# 5V-3_3V_Regulators_Pre-prototype_V2.net
KiCad netlist of a schematic drawn in EAGLE
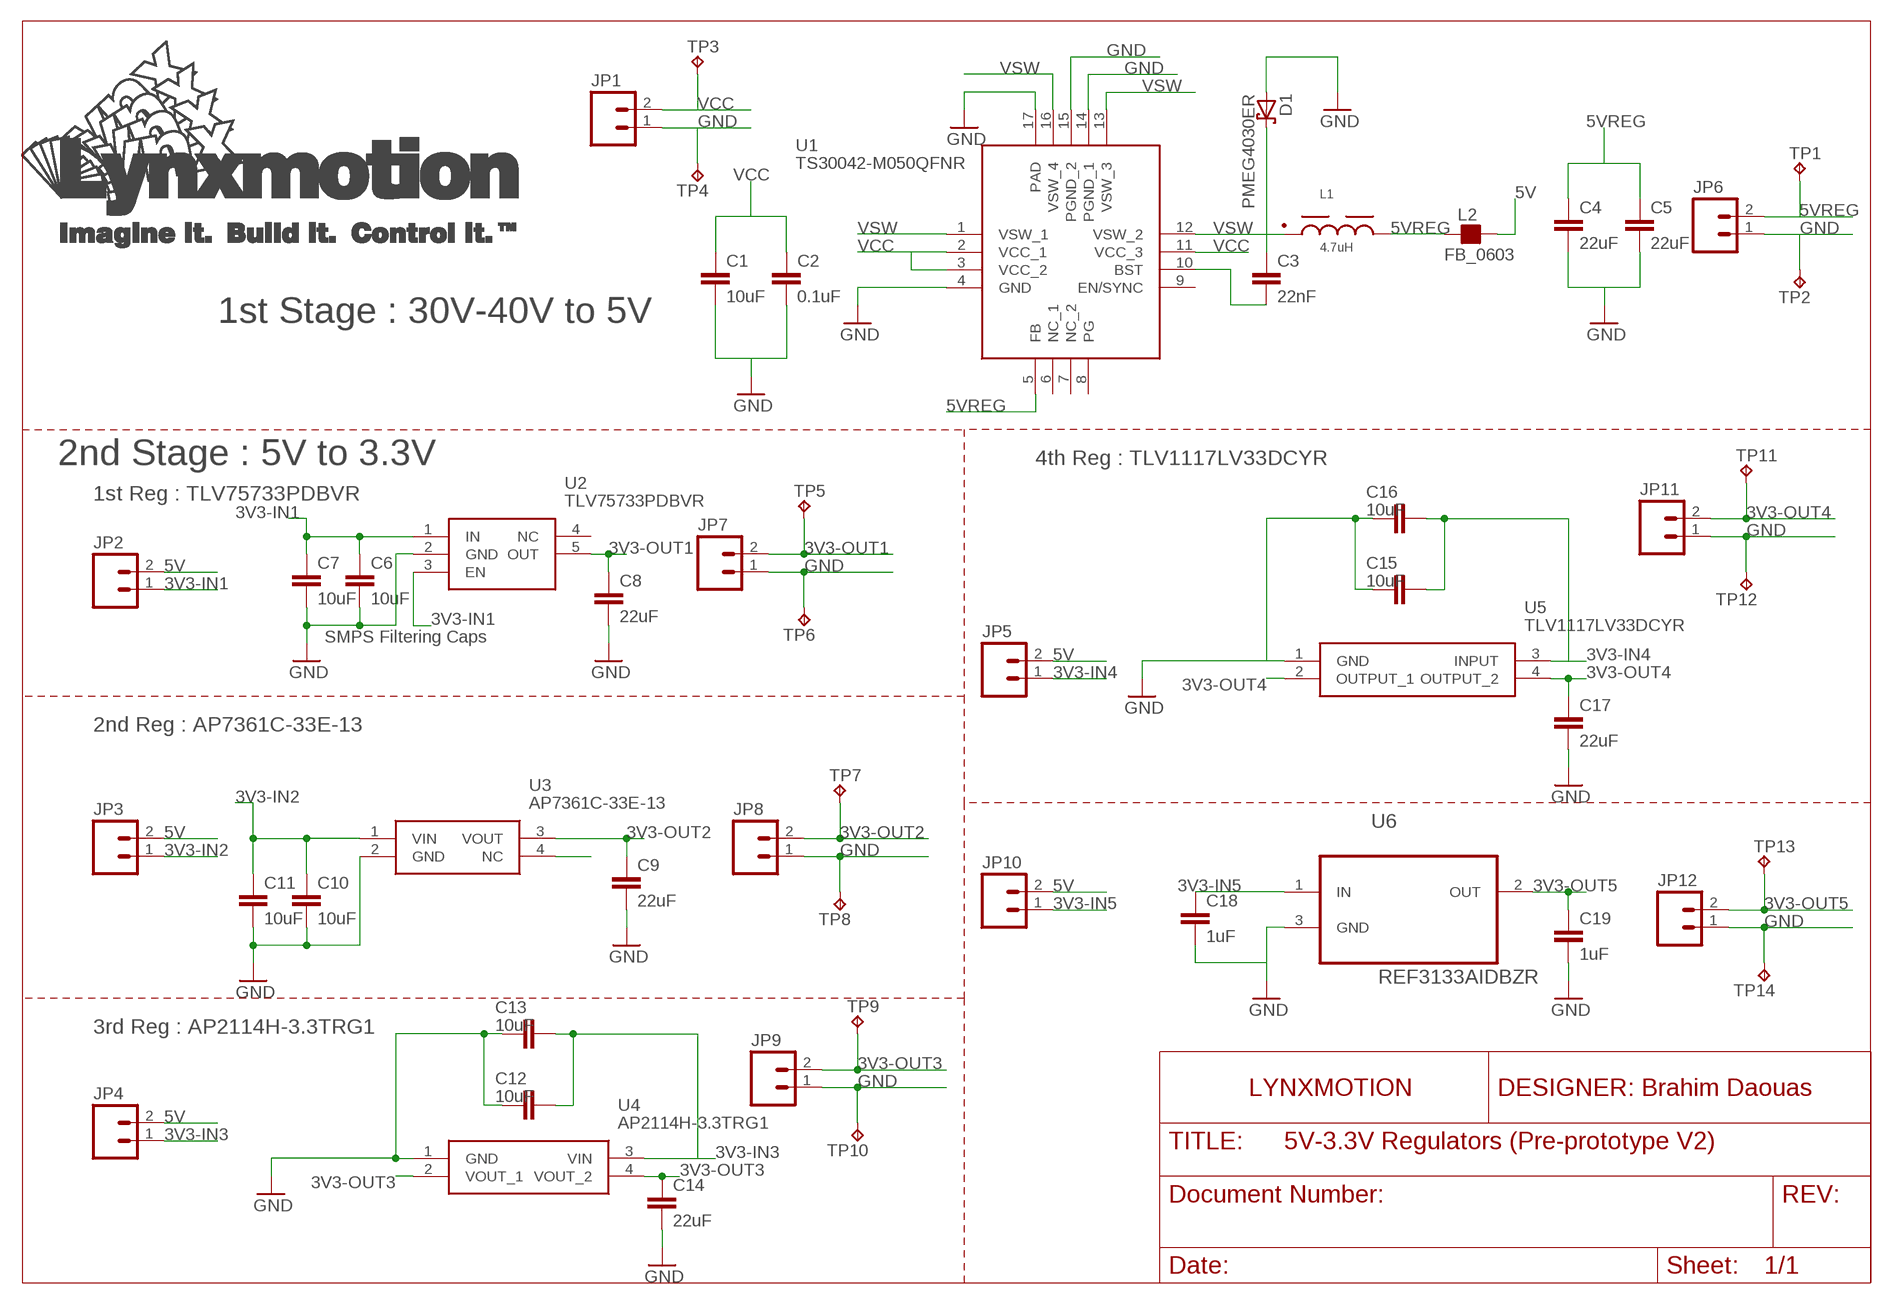
[diagram p0: schematic, sheet 1]

(export (version "E")
  (design (tool "Eeschema 10.0.6"))
  (components
    (comp (ref "C1")
      (value "10uF")
      (footprint "eagle-import:1206")
      (libsource (lib "eagle-import") (part "CAP1206"))
    )
    (comp (ref "C2")
      (value "0.1uF")
      (footprint "eagle-import:0603-CAP")
      (libsource (lib "eagle-import") (part "CAP0603-CAP"))
    )
    (comp (ref "C3")
      (value "22nF")
      (footprint "eagle-import:0402-CAP")
      (libsource (lib "eagle-import") (part "CAP0402-CAP"))
    )
    (comp (ref "C4")
      (value "22uF")
      (footprint "eagle-import:0805")
      (libsource (lib "eagle-import") (part "CAP0805"))
    )
    (comp (ref "C5")
      (value "22uF")
      (footprint "eagle-import:0805")
      (libsource (lib "eagle-import") (part "CAP0805"))
    )
    (comp (ref "C6")
      (value "10uF")
      (footprint "eagle-import:0805")
      (libsource (lib "eagle-import") (part "CAP0805"))
    )
    (comp (ref "C7")
      (value "10uF")
      (footprint "eagle-import:0805")
      (libsource (lib "eagle-import") (part "CAP0805"))
    )
    (comp (ref "C8")
      (value "22uF")
      (footprint "eagle-import:0805")
      (libsource (lib "eagle-import") (part "CAP0805"))
    )
    (comp (ref "C9")
      (value "22uF")
      (footprint "eagle-import:0805")
      (libsource (lib "eagle-import") (part "CAP0805"))
    )
    (comp (ref "C10")
      (value "10uF")
      (footprint "eagle-import:0805")
      (libsource (lib "eagle-import") (part "CAP0805"))
    )
    (comp (ref "C11")
      (value "10uF")
      (footprint "eagle-import:0805")
      (libsource (lib "eagle-import") (part "CAP0805"))
    )
    (comp (ref "C12")
      (value "10uF")
      (footprint "eagle-import:0805")
      (libsource (lib "eagle-import") (part "CAP0805"))
    )
    (comp (ref "C13")
      (value "10uF")
      (footprint "eagle-import:0805")
      (libsource (lib "eagle-import") (part "CAP0805"))
    )
    (comp (ref "C14")
      (value "22uF")
      (footprint "eagle-import:0805")
      (libsource (lib "eagle-import") (part "CAP0805"))
    )
    (comp (ref "C15")
      (value "10uF")
      (footprint "eagle-import:0805")
      (libsource (lib "eagle-import") (part "CAP0805"))
    )
    (comp (ref "C16")
      (value "10uF")
      (footprint "eagle-import:0805")
      (libsource (lib "eagle-import") (part "CAP0805"))
    )
    (comp (ref "C17")
      (value "22uF")
      (footprint "eagle-import:0805")
      (libsource (lib "eagle-import") (part "CAP0805"))
    )
    (comp (ref "C18")
      (value "1uF")
      (footprint "eagle-import:0805")
      (libsource (lib "eagle-import") (part "CAP0805"))
    )
    (comp (ref "C19")
      (value "1uF")
      (footprint "eagle-import:0805")
      (libsource (lib "eagle-import") (part "CAP0805"))
    )
    (comp (ref "D1")
      (value "PMEG4030ER")
      (footprint "eagle-import:SOD123W")
      (libsource (lib "eagle-import") (part "PMEG4030ER"))
    )
    (comp (ref "JP1")
      (value "M02PTH")
      (footprint "eagle-import:1X02")
      (libsource (lib "eagle-import") (part "M02PTH"))
    )
    (comp (ref "JP2")
      (value "M02PTH")
      (footprint "eagle-import:1X02")
      (libsource (lib "eagle-import") (part "M02PTH"))
    )
    (comp (ref "JP3")
      (value "M02PTH")
      (footprint "eagle-import:1X02")
      (libsource (lib "eagle-import") (part "M02PTH"))
    )
    (comp (ref "JP4")
      (value "M02PTH")
      (footprint "eagle-import:1X02")
      (libsource (lib "eagle-import") (part "M02PTH"))
    )
    (comp (ref "JP5")
      (value "M02PTH")
      (footprint "eagle-import:1X02")
      (libsource (lib "eagle-import") (part "M02PTH"))
    )
    (comp (ref "JP6")
      (value "M02PTH")
      (footprint "eagle-import:1X02")
      (libsource (lib "eagle-import") (part "M02PTH"))
    )
    (comp (ref "JP7")
      (value "M02PTH")
      (footprint "eagle-import:1X02")
      (libsource (lib "eagle-import") (part "M02PTH"))
    )
    (comp (ref "JP8")
      (value "M02PTH")
      (footprint "eagle-import:1X02")
      (libsource (lib "eagle-import") (part "M02PTH"))
    )
    (comp (ref "JP9")
      (value "M02PTH")
      (footprint "eagle-import:1X02")
      (libsource (lib "eagle-import") (part "M02PTH"))
    )
    (comp (ref "JP10")
      (value "M02PTH")
      (footprint "eagle-import:1X02")
      (libsource (lib "eagle-import") (part "M02PTH"))
    )
    (comp (ref "JP11")
      (value "M02PTH")
      (footprint "eagle-import:1X02")
      (libsource (lib "eagle-import") (part "M02PTH"))
    )
    (comp (ref "JP12")
      (value "M02PTH")
      (footprint "eagle-import:1X02")
      (libsource (lib "eagle-import") (part "M02PTH"))
    )
    (comp (ref "L1")
      (value "4.7uH")
      (footprint "eagle-import:WE-PD2_5848_5820")
      (libsource (lib "eagle-import") (part "WE-PD2_5848_744774047"))
    )
    (comp (ref "L2")
      (value "FB_0603")
      (footprint "eagle-import:L0603")
      (libsource (lib "eagle-import") (part "FB_0603"))
    )
    (comp (ref "TP1")
      (value "TP-040")
      (footprint "eagle-import:TP-040")
      (libsource (lib "eagle-import") (part "TP-040"))
    )
    (comp (ref "TP2")
      (value "TP-040")
      (footprint "eagle-import:TP-040")
      (libsource (lib "eagle-import") (part "TP-040"))
    )
    (comp (ref "TP3")
      (value "TP-040")
      (footprint "eagle-import:TP-040")
      (libsource (lib "eagle-import") (part "TP-040"))
    )
    (comp (ref "TP4")
      (value "TP-040")
      (footprint "eagle-import:TP-040")
      (libsource (lib "eagle-import") (part "TP-040"))
    )
    (comp (ref "TP5")
      (value "TP-040")
      (footprint "eagle-import:TP-040")
      (libsource (lib "eagle-import") (part "TP-040"))
    )
    (comp (ref "TP6")
      (value "TP-040")
      (footprint "eagle-import:TP-040")
      (libsource (lib "eagle-import") (part "TP-040"))
    )
    (comp (ref "TP7")
      (value "TP-040")
      (footprint "eagle-import:TP-040")
      (libsource (lib "eagle-import") (part "TP-040"))
    )
    (comp (ref "TP8")
      (value "TP-040")
      (footprint "eagle-import:TP-040")
      (libsource (lib "eagle-import") (part "TP-040"))
    )
    (comp (ref "TP9")
      (value "TP-040")
      (footprint "eagle-import:TP-040")
      (libsource (lib "eagle-import") (part "TP-040"))
    )
    (comp (ref "TP10")
      (value "TP-040")
      (footprint "eagle-import:TP-040")
      (libsource (lib "eagle-import") (part "TP-040"))
    )
    (comp (ref "TP11")
      (value "TP-040")
      (footprint "eagle-import:TP-040")
      (libsource (lib "eagle-import") (part "TP-040"))
    )
    (comp (ref "TP12")
      (value "TP-040")
      (footprint "eagle-import:TP-040")
      (libsource (lib "eagle-import") (part "TP-040"))
    )
    (comp (ref "TP13")
      (value "TP-040")
      (footprint "eagle-import:TP-040")
      (libsource (lib "eagle-import") (part "TP-040"))
    )
    (comp (ref "TP14")
      (value "TP-040")
      (footprint "eagle-import:TP-040")
      (libsource (lib "eagle-import") (part "TP-040"))
    )
    (comp (ref "U1")
      (value "TS30042-M050QFNR")
      (footprint "eagle-import:QFN16")
      (libsource (lib "eagle-import") (part "TS30042-M050QFNR"))
    )
    (comp (ref "U2")
      (value "TLV75733PDBVR")
      (footprint "eagle-import:SOT95P280X145-5N")
      (libsource (lib "eagle-import") (part "TLV75733PDBVR"))
    )
    (comp (ref "U3")
      (value "AP7361C-33E-13")
      (footprint "eagle-import:SOT230P700X165-4N")
      (libsource (lib "eagle-import") (part "AP7361C-33E-13"))
    )
    (comp (ref "U4")
      (value "AP2114H-3.3TRG1")
      (footprint "eagle-import:SOT230P700X180-4N")
      (fields
        (field (name "MOUSER_PART_NUMBER") "621-AP2114H-3.3TRG1")
        (field (name "RS_PART_NUMBER") "8283528")
      )
      (libsource (lib "eagle-import") (part "AP2114H-3.3TRG1"))
    )
    (comp (ref "U5")
      (value "TLV1117LV33DCYR")
      (footprint "eagle-import:SOT230P700X180-4N")
      (fields (field (name "MOUSER_PART_NUMBER") "595-TLV1117LV33DCYR"))
      (libsource (lib "eagle-import") (part "TLV1117LV33DCYR"))
    )
    (comp (ref "U6")
      (value "REF3133AIDBZR")
      (footprint "eagle-import:SOT95P237X112-3N")
      (fields (field (name "MF") "Texas Instruments"))
      (libsource (lib "eagle-import") (part "REF3133AIDBZR"))
    )
  )
  (nets
    (net (code "1") (name "/3V3-IN1") (class "Default")
      (node (ref "C6") (pin "1") (pinfunction "1_1") (pintype "passive"))
      (node (ref "C7") (pin "1") (pinfunction "1_1") (pintype "passive"))
      (node (ref "JP2") (pin "1") (pinfunction "1_1") (pintype "passive"))
      (node (ref "U2") (pin "1") (pinfunction "IN_1") (pintype "power_in"))
      (node (ref "U2") (pin "3") (pinfunction "EN_3") (pintype "input"))
    )
    (net (code "2") (name "/3V3-IN2") (class "Default")
      (node (ref "C10") (pin "1") (pinfunction "1_1") (pintype "passive"))
      (node (ref "C11") (pin "1") (pinfunction "1_1") (pintype "passive"))
      (node (ref "JP3") (pin "1") (pinfunction "1_1") (pintype "passive"))
      (node (ref "U3") (pin "1") (pinfunction "VIN_1") (pintype "input"))
    )
    (net (code "3") (name "/3V3-IN3") (class "Default")
      (node (ref "C12") (pin "1") (pinfunction "1_1") (pintype "passive"))
      (node (ref "C13") (pin "1") (pinfunction "1_1") (pintype "passive"))
      (node (ref "JP4") (pin "1") (pinfunction "1_1") (pintype "passive"))
      (node (ref "U4") (pin "3") (pinfunction "VIN_3") (pintype "bidirectional"))
    )
    (net (code "4") (name "/3V3-IN4") (class "Default")
      (node (ref "C15") (pin "1") (pinfunction "1_1") (pintype "passive"))
      (node (ref "C16") (pin "1") (pinfunction "1_1") (pintype "passive"))
      (node (ref "JP5") (pin "1") (pinfunction "1_1") (pintype "passive"))
      (node (ref "U5") (pin "3") (pinfunction "INPUT_3") (pintype "bidirectional"))
    )
    (net (code "5") (name "/3V3-IN5") (class "Default")
      (node (ref "C18") (pin "1") (pinfunction "1_1") (pintype "passive"))
      (node (ref "JP10") (pin "1") (pinfunction "1_1") (pintype "passive"))
      (node (ref "U6") (pin "1") (pinfunction "IN_1") (pintype "power_in"))
    )
    (net (code "6") (name "/3V3-OUT1") (class "Default")
      (node (ref "C8") (pin "1") (pinfunction "1_1") (pintype "passive"))
      (node (ref "JP7") (pin "2") (pinfunction "2_2") (pintype "passive"))
      (node (ref "TP5") (pin "1") (pinfunction "1_1") (pintype "passive"))
      (node (ref "U2") (pin "5") (pinfunction "OUT_5") (pintype "output"))
    )
    (net (code "7") (name "/3V3-OUT2") (class "Default")
      (node (ref "C9") (pin "1") (pinfunction "1_1") (pintype "passive"))
      (node (ref "JP8") (pin "2") (pinfunction "2_2") (pintype "passive"))
      (node (ref "TP7") (pin "1") (pinfunction "1_1") (pintype "passive"))
      (node (ref "U3") (pin "3") (pinfunction "VOUT_3") (pintype "output"))
    )
    (net (code "8") (name "/3V3-OUT3") (class "Default")
      (node (ref "C14") (pin "1") (pinfunction "1_1") (pintype "passive"))
      (node (ref "JP9") (pin "2") (pinfunction "2_2") (pintype "passive"))
      (node (ref "TP9") (pin "1") (pinfunction "1_1") (pintype "passive"))
      (node (ref "U4") (pin "2") (pinfunction "VOUT_1_2") (pintype "bidirectional"))
      (node (ref "U4") (pin "4") (pinfunction "VOUT_2_4") (pintype "bidirectional"))
    )
    (net (code "9") (name "/3V3-OUT4") (class "Default")
      (node (ref "C17") (pin "1") (pinfunction "1_1") (pintype "passive"))
      (node (ref "JP11") (pin "2") (pinfunction "2_2") (pintype "passive"))
      (node (ref "TP11") (pin "1") (pinfunction "1_1") (pintype "passive"))
      (node (ref "U5") (pin "2") (pinfunction "OUTPUT_1_2") (pintype "bidirectional"))
      (node (ref "U5") (pin "4") (pinfunction "OUTPUT_2_4") (pintype "bidirectional"))
    )
    (net (code "10") (name "/3V3-OUT5") (class "Default")
      (node (ref "C19") (pin "1") (pinfunction "1_1") (pintype "passive"))
      (node (ref "JP12") (pin "2") (pinfunction "2_2") (pintype "passive"))
      (node (ref "TP13") (pin "1") (pinfunction "1_1") (pintype "passive"))
      (node (ref "U6") (pin "2") (pinfunction "OUT_2") (pintype "output"))
    )
    (net (code "11") (name "/5V") (class "Default")
      (node (ref "JP10") (pin "2") (pinfunction "2_2") (pintype "passive"))
      (node (ref "JP2") (pin "2") (pinfunction "2_2") (pintype "passive"))
      (node (ref "JP3") (pin "2") (pinfunction "2_2") (pintype "passive"))
      (node (ref "JP4") (pin "2") (pinfunction "2_2") (pintype "passive"))
      (node (ref "JP5") (pin "2") (pinfunction "2_2") (pintype "passive"))
      (node (ref "L2") (pin "2") (pinfunction "2_2") (pintype "passive"))
    )
    (net (code "12") (name "/5VREG") (class "Default")
      (node (ref "C4") (pin "1") (pinfunction "1_1") (pintype "passive"))
      (node (ref "C5") (pin "1") (pinfunction "1_1") (pintype "passive"))
      (node (ref "JP6") (pin "2") (pinfunction "2_2") (pintype "passive"))
      (node (ref "L1") (pin "2") (pinfunction "2_2") (pintype "passive"))
      (node (ref "L2") (pin "1") (pinfunction "1_1") (pintype "passive"))
      (node (ref "TP1") (pin "1") (pinfunction "1_1") (pintype "passive"))
      (node (ref "U1") (pin "5") (pinfunction "FB_5") (pintype "bidirectional"))
    )
    (net (code "13") (name "/VCC") (class "Default")
      (node (ref "C1") (pin "1") (pinfunction "1_1") (pintype "passive"))
      (node (ref "C2") (pin "1") (pinfunction "1_1") (pintype "passive"))
      (node (ref "JP1") (pin "2") (pinfunction "2_2") (pintype "passive"))
      (node (ref "TP3") (pin "1") (pinfunction "1_1") (pintype "passive"))
      (node (ref "U1") (pin "11") (pinfunction "VCC_3_11") (pintype "bidirectional"))
      (node (ref "U1") (pin "2") (pinfunction "VCC_1_2") (pintype "bidirectional"))
      (node (ref "U1") (pin "3") (pinfunction "VCC_2_3") (pintype "bidirectional"))
    )
    (net (code "14") (name "/VSW") (class "Default")
      (node (ref "C3") (pin "1") (pinfunction "1_1") (pintype "passive"))
      (node (ref "D1") (pin "1") (pinfunction "K_1") (pintype "passive"))
      (node (ref "L1") (pin "1") (pinfunction "1_1") (pintype "passive"))
      (node (ref "U1") (pin "1") (pinfunction "VSW_1_1") (pintype "bidirectional"))
      (node (ref "U1") (pin "12") (pinfunction "VSW_2_12") (pintype "bidirectional"))
      (node (ref "U1") (pin "13") (pinfunction "VSW_3_13") (pintype "bidirectional"))
      (node (ref "U1") (pin "16") (pinfunction "VSW_4_16") (pintype "bidirectional"))
    )
    (net (code "15") (name "GND") (class "Default")
      (node (ref "C1") (pin "2") (pinfunction "2_2") (pintype "passive"))
      (node (ref "C10") (pin "2") (pinfunction "2_2") (pintype "passive"))
      (node (ref "C11") (pin "2") (pinfunction "2_2") (pintype "passive"))
      (node (ref "C12") (pin "2") (pinfunction "2_2") (pintype "passive"))
      (node (ref "C13") (pin "2") (pinfunction "2_2") (pintype "passive"))
      (node (ref "C14") (pin "2") (pinfunction "2_2") (pintype "passive"))
      (node (ref "C15") (pin "2") (pinfunction "2_2") (pintype "passive"))
      (node (ref "C16") (pin "2") (pinfunction "2_2") (pintype "passive"))
      (node (ref "C17") (pin "2") (pinfunction "2_2") (pintype "passive"))
      (node (ref "C18") (pin "2") (pinfunction "2_2") (pintype "passive"))
      (node (ref "C19") (pin "2") (pinfunction "2_2") (pintype "passive"))
      (node (ref "C2") (pin "2") (pinfunction "2_2") (pintype "passive"))
      (node (ref "C4") (pin "2") (pinfunction "2_2") (pintype "passive"))
      (node (ref "C5") (pin "2") (pinfunction "2_2") (pintype "passive"))
      (node (ref "C6") (pin "2") (pinfunction "2_2") (pintype "passive"))
      (node (ref "C7") (pin "2") (pinfunction "2_2") (pintype "passive"))
      (node (ref "C8") (pin "2") (pinfunction "2_2") (pintype "passive"))
      (node (ref "C9") (pin "2") (pinfunction "2_2") (pintype "passive"))
      (node (ref "D1") (pin "2") (pinfunction "A_2") (pintype "passive"))
      (node (ref "JP1") (pin "1") (pinfunction "1_1") (pintype "passive"))
      (node (ref "JP11") (pin "1") (pinfunction "1_1") (pintype "passive"))
      (node (ref "JP12") (pin "1") (pinfunction "1_1") (pintype "passive"))
      (node (ref "JP6") (pin "1") (pinfunction "1_1") (pintype "passive"))
      (node (ref "JP7") (pin "1") (pinfunction "1_1") (pintype "passive"))
      (node (ref "JP8") (pin "1") (pinfunction "1_1") (pintype "passive"))
      (node (ref "JP9") (pin "1") (pinfunction "1_1") (pintype "passive"))
      (node (ref "TP10") (pin "1") (pinfunction "1_1") (pintype "passive"))
      (node (ref "TP12") (pin "1") (pinfunction "1_1") (pintype "passive"))
      (node (ref "TP14") (pin "1") (pinfunction "1_1") (pintype "passive"))
      (node (ref "TP2") (pin "1") (pinfunction "1_1") (pintype "passive"))
      (node (ref "TP4") (pin "1") (pinfunction "1_1") (pintype "passive"))
      (node (ref "TP6") (pin "1") (pinfunction "1_1") (pintype "passive"))
      (node (ref "TP8") (pin "1") (pinfunction "1_1") (pintype "passive"))
      (node (ref "U1") (pin "14") (pinfunction "PGND_1_14") (pintype "bidirectional"))
      (node (ref "U1") (pin "15") (pinfunction "PGND_2_15") (pintype "bidirectional"))
      (node (ref "U1") (pin "17") (pinfunction "PAD_17") (pintype "bidirectional"))
      (node (ref "U1") (pin "4") (pinfunction "GND_4") (pintype "bidirectional"))
      (node (ref "U2") (pin "2") (pinfunction "GND_2") (pintype "power_in"))
      (node (ref "U3") (pin "2") (pinfunction "GND_2") (pintype "power_in"))
      (node (ref "U4") (pin "1") (pinfunction "GND_1") (pintype "bidirectional"))
      (node (ref "U5") (pin "1") (pinfunction "GND_1") (pintype "bidirectional"))
      (node (ref "U6") (pin "3") (pinfunction "GND_3") (pintype "passive"))
    )
    (net (code "16") (name "Net-(U1-BST)") (class "Default")
      (node (ref "C3") (pin "2") (pinfunction "2_2") (pintype "passive"))
      (node (ref "U1") (pin "10") (pinfunction "BST_10") (pintype "bidirectional"))
    )
    (net (code "17") (name "unconnected-(U1-EN{slash}SYNC-Pad9)") (class "Default")
      (node (ref "U1") (pin "9") (pinfunction "EN/SYNC_9") (pintype "bidirectional"))
    )
    (net (code "18") (name "unconnected-(U1-NC_1-Pad6)") (class "Default")
      (node (ref "U1") (pin "6") (pinfunction "NC_1_6") (pintype "bidirectional"))
    )
    (net (code "19") (name "unconnected-(U1-NC_2-Pad7)") (class "Default")
      (node (ref "U1") (pin "7") (pinfunction "NC_2_7") (pintype "bidirectional"))
    )
    (net (code "20") (name "unconnected-(U1-PG-Pad8)") (class "Default")
      (node (ref "U1") (pin "8") (pinfunction "PG_8") (pintype "bidirectional"))
    )
    (net (code "21") (name "unconnected-(U2-NC-Pad4)") (class "Default")
      (node (ref "U2") (pin "4") (pinfunction "NC_4") (pintype "no_connect"))
    )
    (net (code "22") (name "unconnected-(U3-NC-Pad4)") (class "Default")
      (node (ref "U3") (pin "4") (pinfunction "NC_4") (pintype "no_connect"))
    )
  )
)
